# Ktir.net
KiCad netlist of a schematic drawn in Altium Designer
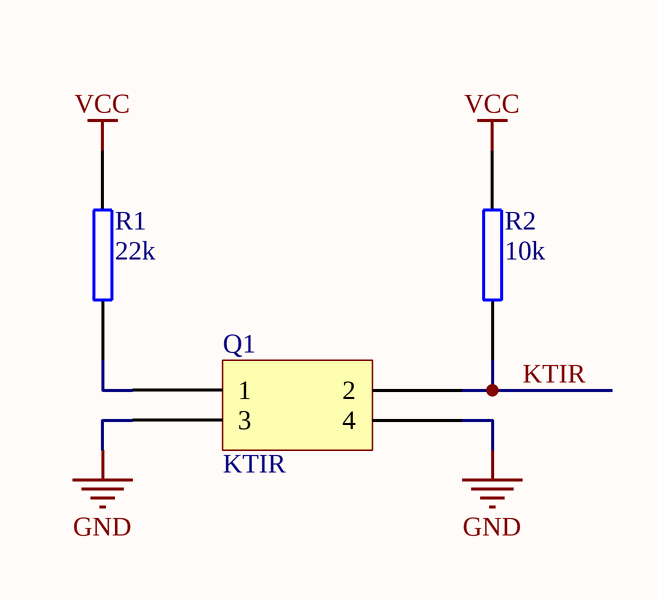
[diagram p0: Ktir.SchDoc]

(export (version "E")
  (design (tool "Eeschema 10.0.6"))
  (components
    (comp (ref "Q1") (value "KTIR") (footprint "KTIR") (libsource (lib "juziuLibrary") (part "KTIR")))
    (comp (ref "R1") (value "22k") (footprint "0805 RES") (libsource (lib "Integrated_Library1") (part "R")))
    (comp (ref "R2") (value "10k") (footprint "0805 RES") (libsource (lib "Integrated_Library1") (part "R")))
  )
  (nets
    (net (code "1") (name "/KTIR") (class "Default")
      (node (ref "Q1") (pin "2") (pinfunction "2_2") (pintype "passive"))
      (node (ref "R2") (pin "2") (pinfunction "2_2") (pintype "passive"))
    )
    (net (code "2") (name "GND") (class "Default")
      (node (ref "Q1") (pin "3") (pinfunction "3_3") (pintype "passive"))
      (node (ref "Q1") (pin "4") (pinfunction "4_4") (pintype "passive"))
    )
    (net (code "3") (name "Net-(Q1-Pad1)") (class "Default")
      (node (ref "Q1") (pin "1") (pinfunction "1_1") (pintype "passive"))
      (node (ref "R1") (pin "2") (pinfunction "2_2") (pintype "passive"))
    )
    (net (code "4") (name "VCC") (class "Default")
      (node (ref "R1") (pin "1") (pinfunction "1_1") (pintype "passive"))
      (node (ref "R2") (pin "1") (pinfunction "1_1") (pintype "passive"))
    )
  )
)
